# object_1.net
KiCad netlist of a schematic drawn in EAGLE
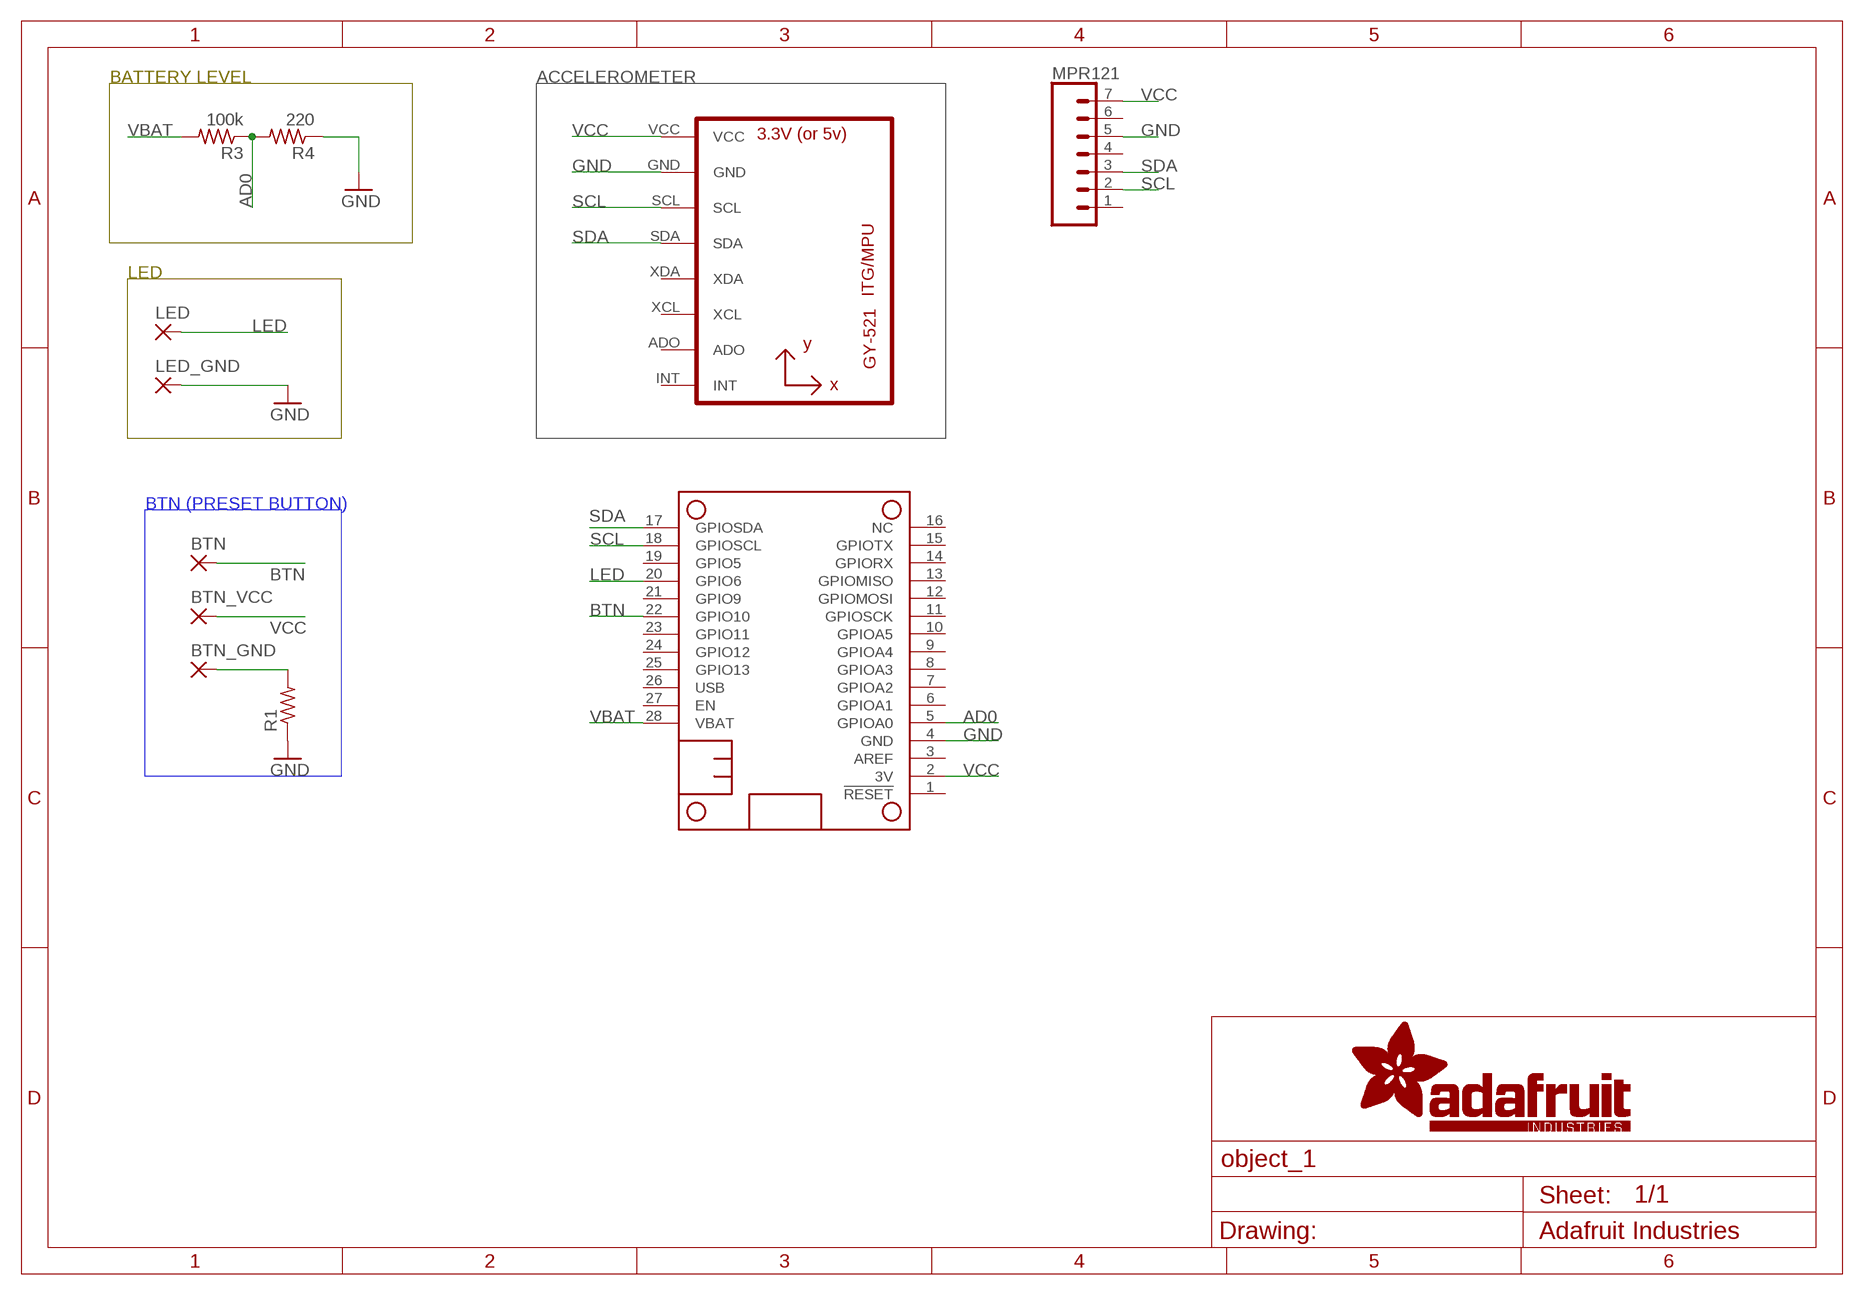
[diagram p0: schematic, sheet 1]

(export (version "E")
  (design (tool "Eeschema 10.0.6"))
  (components
    (comp (ref "BTN")
      (value "2,15/1,0")
      (footprint "eagle-import:2,15_1,0")
      (libsource (lib "eagle-import") (part "2,15/1,0"))
    )
    (comp (ref "BTN_GND")
      (value "2,15/1,0")
      (footprint "eagle-import:2,15_1,0")
      (libsource (lib "eagle-import") (part "2,15/1,0"))
    )
    (comp (ref "BTN_VCC")
      (value "2,15/1,0")
      (footprint "eagle-import:2,15_1,0")
      (libsource (lib "eagle-import") (part "2,15/1,0"))
    )
    (comp (ref "LED")
      (value "2,15/1,0")
      (footprint "eagle-import:2,15_1,0")
      (libsource (lib "eagle-import") (part "2,15/1,0"))
    )
    (comp (ref "LED_GND")
      (value "2,15/1,0")
      (footprint "eagle-import:2,15_1,0")
      (libsource (lib "eagle-import") (part "2,15/1,0"))
    )
    (comp (ref "MPR121")
      (value "CONN_07NO_SILK")
      (footprint "eagle-import:1X07_NO_SILK")
      (libsource (lib "eagle-import") (part "CONN_07NO_SILK"))
    )
    (comp (ref "MS1")
      (value "FEATHERWING")
      (footprint "eagle-import:FEATHERWING")
      (libsource (lib "eagle-import") (part "FEATHERWING"))
    )
    (comp (ref "R1")
      (value "R-US_0204/5")
      (footprint "eagle-import:0204_5")
      (libsource (lib "eagle-import") (part "R-US_0204/5"))
    )
    (comp (ref "R3")
      (value "100k")
      (footprint "eagle-import:0204_5")
      (libsource (lib "eagle-import") (part "R-US_0204/5"))
    )
    (comp (ref "R4")
      (value "220")
      (footprint "eagle-import:0204_5")
      (libsource (lib "eagle-import") (part "R-US_0204/5"))
    )
    (comp (ref "U1")
      (value "GY-521MPU6050")
      (footprint "eagle-import:GY-521")
      (libsource (lib "eagle-import") (part "GY-521MPU6050"))
    )
  )
  (nets
    (net (code "1") (name "/AD0") (class "Default")
      (node (ref "MS1") (pin "5") (pinfunction "GPIOA0_5") (pintype "bidirectional"))
      (node (ref "R3") (pin "1") (pinfunction "1_1") (pintype "passive"))
      (node (ref "R4") (pin "2") (pinfunction "2_2") (pintype "passive"))
    )
    (net (code "2") (name "/BTN") (class "Default")
      (node (ref "BTN") (pin "1") (pinfunction "P_1") (pintype "passive"))
      (node (ref "MS1") (pin "22") (pinfunction "GPIO10_22") (pintype "bidirectional"))
    )
    (net (code "3") (name "/LED") (class "Default")
      (node (ref "LED") (pin "1") (pinfunction "P_1") (pintype "passive"))
      (node (ref "MS1") (pin "20") (pinfunction "GPIO6_20") (pintype "bidirectional"))
    )
    (net (code "4") (name "/SCL") (class "Default")
      (node (ref "MPR121") (pin "2") (pinfunction "2_2") (pintype "passive"))
      (node (ref "MS1") (pin "18") (pinfunction "GPIOSCL_18") (pintype "bidirectional"))
      (node (ref "U1") (pin "SCL") (pinfunction "SCL_SCL") (pintype "bidirectional"))
    )
    (net (code "5") (name "/SDA") (class "Default")
      (node (ref "MPR121") (pin "3") (pinfunction "3_3") (pintype "passive"))
      (node (ref "MS1") (pin "17") (pinfunction "GPIOSDA_17") (pintype "bidirectional"))
      (node (ref "U1") (pin "SDA") (pinfunction "SDA_SDA") (pintype "bidirectional"))
    )
    (net (code "6") (name "/USB") (class "Default")
      (node (ref "MS1") (pin "26") (pinfunction "USB_26") (pintype "power_in"))
    )
    (net (code "7") (name "/VBAT") (class "Default")
      (node (ref "MS1") (pin "28") (pinfunction "VBAT_28") (pintype "power_in"))
      (node (ref "R3") (pin "2") (pinfunction "2_2") (pintype "passive"))
    )
    (net (code "8") (name "/VCC") (class "Default")
      (node (ref "BTN_VCC") (pin "1") (pinfunction "P_1") (pintype "passive"))
      (node (ref "MPR121") (pin "7") (pinfunction "7_7") (pintype "passive"))
      (node (ref "MS1") (pin "2") (pinfunction "3V_2") (pintype "power_in"))
      (node (ref "U1") (pin "VCC") (pinfunction "VCC_VCC") (pintype "bidirectional"))
    )
    (net (code "9") (name "GND") (class "Default")
      (node (ref "LED_GND") (pin "1") (pinfunction "P_1") (pintype "passive"))
      (node (ref "MPR121") (pin "5") (pinfunction "5_5") (pintype "passive"))
      (node (ref "MS1") (pin "4") (pinfunction "GND_4") (pintype "power_in"))
      (node (ref "R1") (pin "1") (pinfunction "1_1") (pintype "passive"))
      (node (ref "R4") (pin "1") (pinfunction "1_1") (pintype "passive"))
      (node (ref "U1") (pin "GND") (pinfunction "GND_GND") (pintype "bidirectional"))
    )
    (net (code "10") (name "Net-(BTN_GND-P)") (class "Default")
      (node (ref "BTN_GND") (pin "1") (pinfunction "P_1") (pintype "passive"))
      (node (ref "R1") (pin "2") (pinfunction "2_2") (pintype "passive"))
    )
    (net (code "11") (name "unconnected-(MPR121-Pad1)") (class "Default")
      (node (ref "MPR121") (pin "1") (pinfunction "1_1") (pintype "passive"))
    )
    (net (code "12") (name "unconnected-(MPR121-Pad4)") (class "Default")
      (node (ref "MPR121") (pin "4") (pinfunction "4_4") (pintype "passive"))
    )
    (net (code "13") (name "unconnected-(MPR121-Pad6)") (class "Default")
      (node (ref "MPR121") (pin "6") (pinfunction "6_6") (pintype "passive"))
    )
    (net (code "14") (name "unconnected-(MS1-AREF-Pad3)") (class "Default")
      (node (ref "MS1") (pin "3") (pinfunction "AREF_3") (pintype "passive"))
    )
    (net (code "15") (name "unconnected-(MS1-EN-Pad27)") (class "Default")
      (node (ref "MS1") (pin "27") (pinfunction "EN_27") (pintype "passive"))
    )
    (net (code "16") (name "unconnected-(MS1-GPIO5-Pad19)") (class "Default")
      (node (ref "MS1") (pin "19") (pinfunction "GPIO5_19") (pintype "bidirectional"))
    )
    (net (code "17") (name "unconnected-(MS1-GPIO9-Pad21)") (class "Default")
      (node (ref "MS1") (pin "21") (pinfunction "GPIO9_21") (pintype "bidirectional"))
    )
    (net (code "18") (name "unconnected-(MS1-GPIO11-Pad23)") (class "Default")
      (node (ref "MS1") (pin "23") (pinfunction "GPIO11_23") (pintype "bidirectional"))
    )
    (net (code "19") (name "unconnected-(MS1-GPIO12-Pad24)") (class "Default")
      (node (ref "MS1") (pin "24") (pinfunction "GPIO12_24") (pintype "bidirectional"))
    )
    (net (code "20") (name "unconnected-(MS1-GPIO13-Pad25)") (class "Default")
      (node (ref "MS1") (pin "25") (pinfunction "GPIO13_25") (pintype "bidirectional"))
    )
    (net (code "21") (name "unconnected-(MS1-GPIOA1-Pad6)") (class "Default")
      (node (ref "MS1") (pin "6") (pinfunction "GPIOA1_6") (pintype "bidirectional"))
    )
    (net (code "22") (name "unconnected-(MS1-GPIOA2-Pad7)") (class "Default")
      (node (ref "MS1") (pin "7") (pinfunction "GPIOA2_7") (pintype "bidirectional"))
    )
    (net (code "23") (name "unconnected-(MS1-GPIOA3-Pad8)") (class "Default")
      (node (ref "MS1") (pin "8") (pinfunction "GPIOA3_8") (pintype "bidirectional"))
    )
    (net (code "24") (name "unconnected-(MS1-GPIOA4-Pad9)") (class "Default")
      (node (ref "MS1") (pin "9") (pinfunction "GPIOA4_9") (pintype "bidirectional"))
    )
    (net (code "25") (name "unconnected-(MS1-GPIOA5-Pad10)") (class "Default")
      (node (ref "MS1") (pin "10") (pinfunction "GPIOA5_10") (pintype "bidirectional"))
    )
    (net (code "26") (name "unconnected-(MS1-GPIOMISO-Pad13)") (class "Default")
      (node (ref "MS1") (pin "13") (pinfunction "GPIOMISO_13") (pintype "bidirectional"))
    )
    (net (code "27") (name "unconnected-(MS1-GPIOMOSI-Pad12)") (class "Default")
      (node (ref "MS1") (pin "12") (pinfunction "GPIOMOSI_12") (pintype "bidirectional"))
    )
    (net (code "28") (name "unconnected-(MS1-GPIORX-Pad14)") (class "Default")
      (node (ref "MS1") (pin "14") (pinfunction "GPIORX_14") (pintype "bidirectional"))
    )
    (net (code "29") (name "unconnected-(MS1-GPIOSCK-Pad11)") (class "Default")
      (node (ref "MS1") (pin "11") (pinfunction "GPIOSCK_11") (pintype "bidirectional"))
    )
    (net (code "30") (name "unconnected-(MS1-GPIOTX-Pad15)") (class "Default")
      (node (ref "MS1") (pin "15") (pinfunction "GPIOTX_15") (pintype "bidirectional"))
    )
    (net (code "31") (name "unconnected-(MS1-NC-Pad16)") (class "Default")
      (node (ref "MS1") (pin "16") (pinfunction "NC_16") (pintype "passive"))
    )
    (net (code "32") (name "unconnected-(MS1-~{RESET}-Pad1)") (class "Default")
      (node (ref "MS1") (pin "1") (pinfunction "~{RESET}_1") (pintype "input"))
    )
    (net (code "33") (name "unconnected-(U1-PadADO)") (class "Default")
      (node (ref "U1") (pin "ADO") (pinfunction "ADO_ADO") (pintype "bidirectional"))
    )
    (net (code "34") (name "unconnected-(U1-PadINT)") (class "Default")
      (node (ref "U1") (pin "INT") (pinfunction "INT_INT") (pintype "bidirectional"))
    )
    (net (code "35") (name "unconnected-(U1-PadXCL)") (class "Default")
      (node (ref "U1") (pin "XCL") (pinfunction "XCL_XCL") (pintype "bidirectional"))
    )
    (net (code "36") (name "unconnected-(U1-PadXDA)") (class "Default")
      (node (ref "U1") (pin "XDA") (pinfunction "XDA_XDA") (pintype "bidirectional"))
    )
  )
)
